# Blueboard_Pro_v1_0.net
KiCad netlist of a schematic drawn in EAGLE
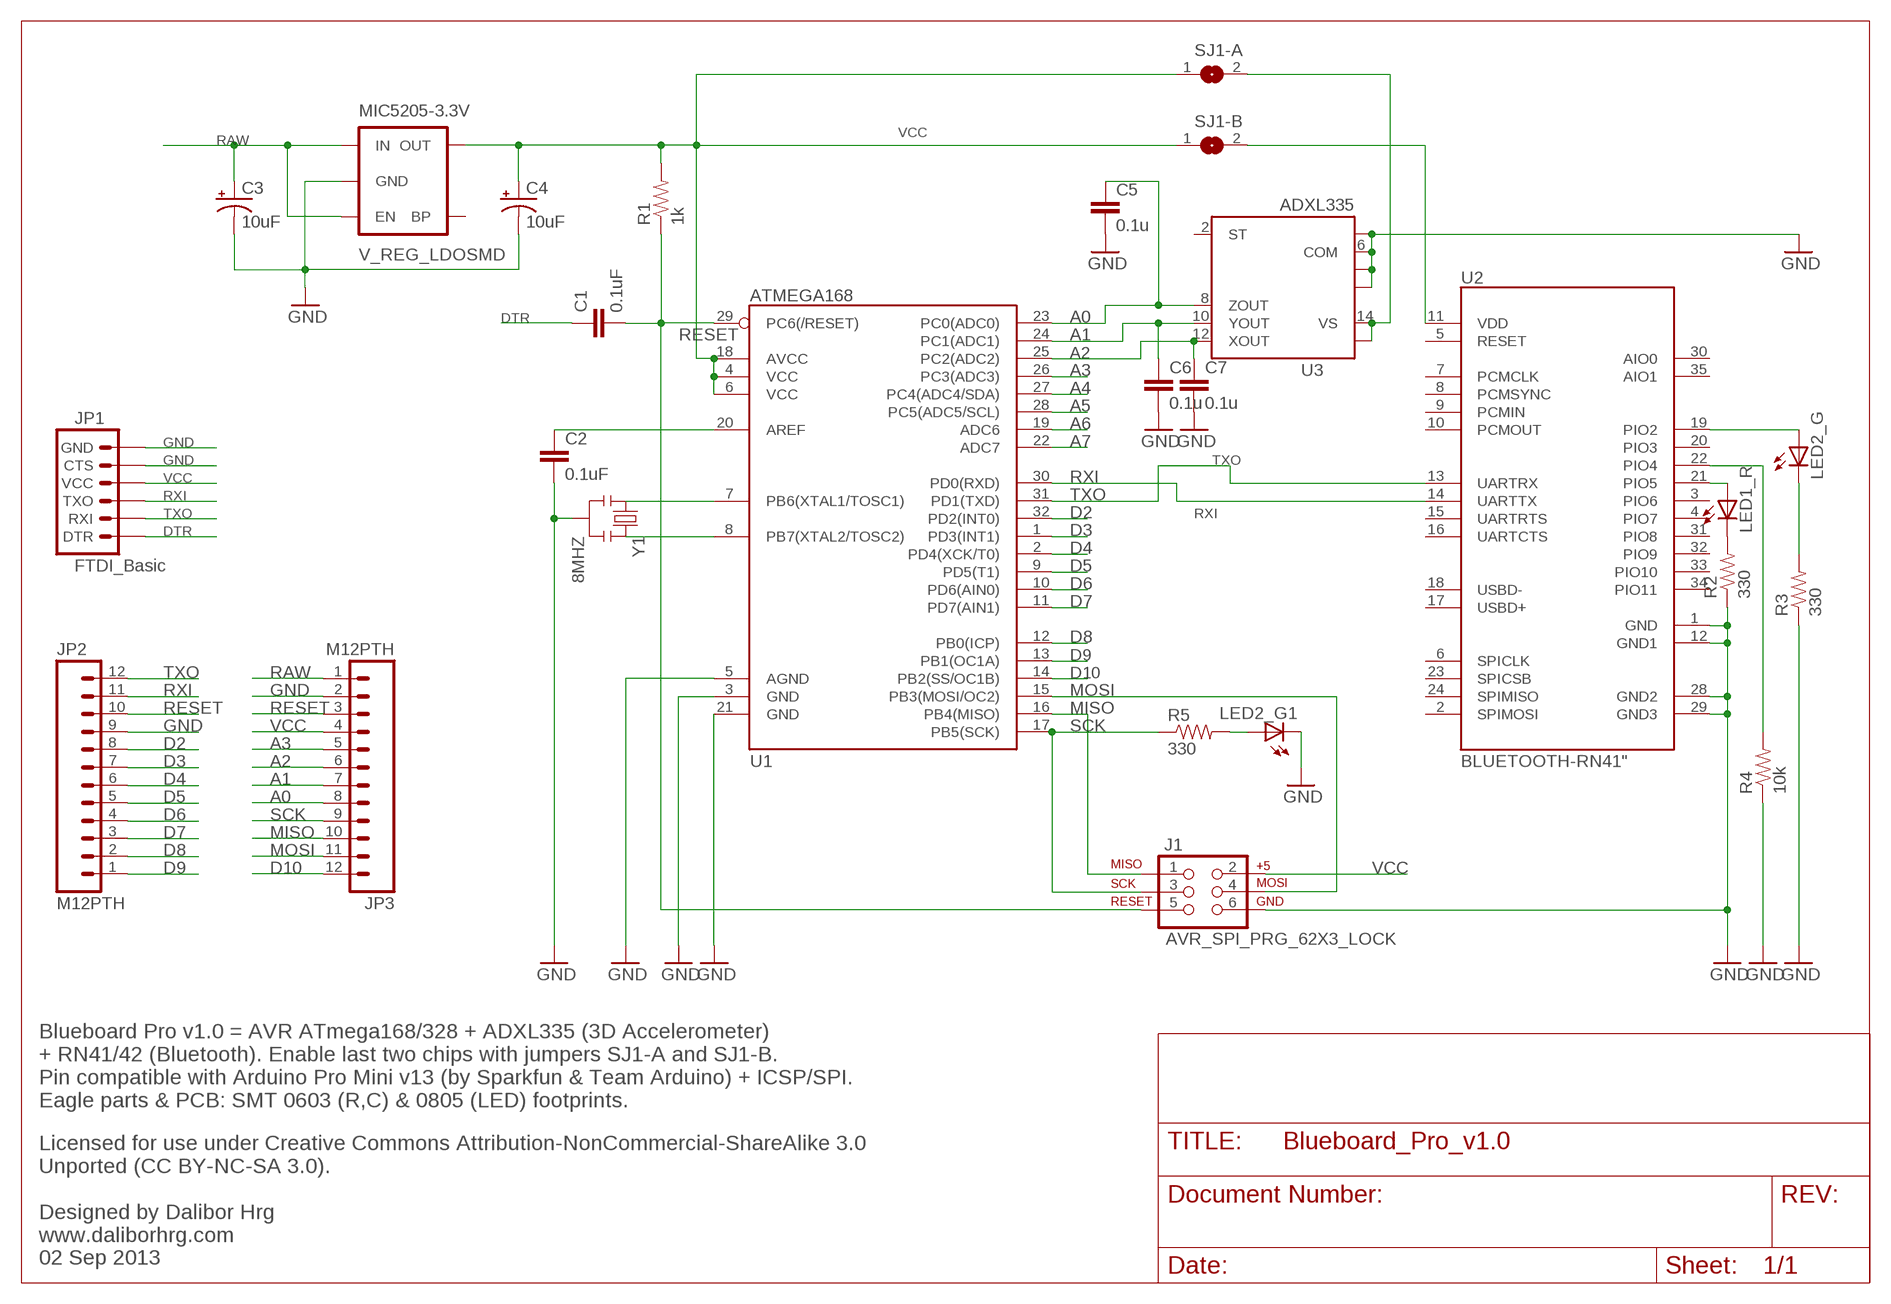
[diagram p0: schematic, sheet 1]

(export (version "E")
  (design (tool "Eeschema 10.0.6"))
  (components
    (comp (ref "C1")
      (value "0.1uF")
      (footprint "eagle-import:0603-CAP")
      (libsource (lib "eagle-import") (part "SparkFun-Passives_CAP0603-CAP"))
    )
    (comp (ref "C2")
      (value "0.1uF")
      (footprint "eagle-import:0603-CAP")
      (libsource (lib "eagle-import") (part "CAP0603-CAP"))
    )
    (comp (ref "C3")
      (value "10uF")
      (footprint "eagle-import:EIA3216")
      (libsource (lib "eagle-import") (part "10UF-16V-10%(TANT)"))
    )
    (comp (ref "C4")
      (value "10uF")
      (footprint "eagle-import:EIA3216")
      (libsource (lib "eagle-import") (part "10UF-16V-10%(TANT)"))
    )
    (comp (ref "C5")
      (value "0.1u")
      (footprint "eagle-import:0603-CAP")
      (libsource (lib "eagle-import") (part "SparkFun-Passives_CAP0603-CAP"))
    )
    (comp (ref "C6")
      (value "0.1u")
      (footprint "eagle-import:0603-CAP")
      (libsource (lib "eagle-import") (part "SparkFun-Passives_CAP0603-CAP"))
    )
    (comp (ref "C7")
      (value "0.1u")
      (footprint "eagle-import:0603-CAP")
      (libsource (lib "eagle-import") (part "SparkFun-Passives_CAP0603-CAP"))
    )
    (comp (ref "J1")
      (value "AVR_SPI_PRG_62X3_LOCK")
      (footprint "eagle-import:2X3_LOCK")
      (libsource (lib "eagle-import") (part "AVR_SPI_PRG_62X3_LOCK"))
    )
    (comp (ref "JP1")
      (value "FTDI_Basic")
      (footprint "eagle-import:1X06")
      (libsource (lib "eagle-import") (part "ARDUINO_SERIAL_PROGRAMPTH"))
    )
    (comp (ref "JP2")
      (value "M12PTH")
      (footprint "eagle-import:1X12")
      (libsource (lib "eagle-import") (part "M12PTH"))
    )
    (comp (ref "JP3")
      (value "M12PTH")
      (footprint "eagle-import:1X12")
      (libsource (lib "eagle-import") (part "M12PTH"))
    )
    (comp (ref "LED1_R")
      (value "LEDCHIP-LED0805")
      (footprint "eagle-import:CHIP-LED0805")
      (libsource (lib "eagle-import") (part "LEDCHIP-LED0805"))
    )
    (comp (ref "LED2_G")
      (value "LEDCHIP-LED0805")
      (footprint "eagle-import:CHIP-LED0805")
      (libsource (lib "eagle-import") (part "LEDCHIP-LED0805"))
    )
    (comp (ref "LED2_G1")
      (value "LEDCHIP-LED0805")
      (footprint "eagle-import:CHIP-LED0805")
      (libsource (lib "eagle-import") (part "LEDCHIP-LED0805"))
    )
    (comp (ref "MIC5205-3.3V")
      (value "V_REG_LDOSMD")
      (footprint "eagle-import:SOT23-5")
      (libsource (lib "eagle-import") (part "V_REG_LDOSMD"))
    )
    (comp (ref "R1")
      (value "1k")
      (footprint "eagle-import:0603-RES")
      (libsource (lib "eagle-import") (part "1K-1%"))
    )
    (comp (ref "R2")
      (value "330")
      (footprint "eagle-import:0603-RES")
      (libsource (lib "eagle-import") (part "RESISTOR0603-RES"))
    )
    (comp (ref "R3")
      (value "330")
      (footprint "eagle-import:0603-RES")
      (libsource (lib "eagle-import") (part "RESISTOR0603-RES"))
    )
    (comp (ref "R4")
      (value "10k")
      (footprint "eagle-import:0603-RES")
      (libsource (lib "eagle-import") (part "RESISTOR0603"))
    )
    (comp (ref "R5")
      (value "330")
      (footprint "eagle-import:0603-RES")
      (libsource (lib "eagle-import") (part "RESISTOR0603-RES"))
    )
    (comp (ref "SJ1-A")
      (value "SJ")
      (footprint "eagle-import:SJ")
      (libsource (lib "eagle-import") (part "SJ"))
    )
    (comp (ref "SJ1-B")
      (value "SJ")
      (footprint "eagle-import:SJ")
      (libsource (lib "eagle-import") (part "SJ"))
    )
    (comp (ref "U1")
      (value "ATMEGA168")
      (footprint "eagle-import:TQFP32-08")
      (libsource (lib "eagle-import") (part "ATMEGA168"))
    )
    (comp (ref "U2")
      (value "BLUETOOTH-RN41\"")
      (footprint "eagle-import:RN41")
      (libsource (lib "eagle-import") (part "BLUETOOTH-RN41{dblquote}"))
    )
    (comp (ref "U3")
      (value "ADXL335")
      (footprint "eagle-import:LFCSP-16")
      (libsource (lib "eagle-import") (part "ADXL335"))
    )
    (comp (ref "Y1")
      (value "8MHZ")
      (footprint "eagle-import:RESONATOR-SMD")
      (libsource (lib "eagle-import") (part "RESONATOR8MHZ"))
    )
  )
  (nets
    (net (code "1") (name "/A0") (class "Default")
      (node (ref "C5") (pin "1") (pinfunction "1_1") (pintype "passive"))
      (node (ref "JP3") (pin "8") (pinfunction "8_8") (pintype "passive"))
      (node (ref "U1") (pin "23") (pinfunction "PC0(ADC0)_23") (pintype "bidirectional"))
      (node (ref "U3") (pin "8") (pinfunction "ZOUT_8") (pintype "bidirectional"))
    )
    (net (code "2") (name "/A1") (class "Default")
      (node (ref "C6") (pin "1") (pinfunction "1_1") (pintype "passive"))
      (node (ref "JP3") (pin "7") (pinfunction "7_7") (pintype "passive"))
      (node (ref "U1") (pin "24") (pinfunction "PC1(ADC1)_24") (pintype "bidirectional"))
      (node (ref "U3") (pin "10") (pinfunction "YOUT_10") (pintype "bidirectional"))
    )
    (net (code "3") (name "/A2") (class "Default")
      (node (ref "C7") (pin "1") (pinfunction "1_1") (pintype "passive"))
      (node (ref "JP3") (pin "6") (pinfunction "6_6") (pintype "passive"))
      (node (ref "U1") (pin "25") (pinfunction "PC2(ADC2)_25") (pintype "bidirectional"))
      (node (ref "U3") (pin "12") (pinfunction "XOUT_12") (pintype "bidirectional"))
    )
    (net (code "4") (name "/A3") (class "Default")
      (node (ref "JP3") (pin "5") (pinfunction "5_5") (pintype "passive"))
      (node (ref "U1") (pin "26") (pinfunction "PC3(ADC3)_26") (pintype "bidirectional"))
    )
    (net (code "5") (name "/A4") (class "Default")
      (node (ref "U1") (pin "27") (pinfunction "PC4(ADC4/SDA)_27") (pintype "bidirectional"))
    )
    (net (code "6") (name "/A5") (class "Default")
      (node (ref "U1") (pin "28") (pinfunction "PC5(ADC5/SCL)_28") (pintype "bidirectional"))
    )
    (net (code "7") (name "/A6") (class "Default")
      (node (ref "U1") (pin "19") (pinfunction "ADC6_19") (pintype "bidirectional"))
    )
    (net (code "8") (name "/A7") (class "Default")
      (node (ref "U1") (pin "22") (pinfunction "ADC7_22") (pintype "bidirectional"))
    )
    (net (code "9") (name "/D2") (class "Default")
      (node (ref "JP2") (pin "8") (pinfunction "8_8") (pintype "passive"))
      (node (ref "U1") (pin "32") (pinfunction "PD2(INT0)_32") (pintype "bidirectional"))
    )
    (net (code "10") (name "/D3") (class "Default")
      (node (ref "JP2") (pin "7") (pinfunction "7_7") (pintype "passive"))
      (node (ref "U1") (pin "1") (pinfunction "PD3(INT1)_1") (pintype "bidirectional"))
    )
    (net (code "11") (name "/D4") (class "Default")
      (node (ref "JP2") (pin "6") (pinfunction "6_6") (pintype "passive"))
      (node (ref "U1") (pin "2") (pinfunction "PD4(XCK/T0)_2") (pintype "bidirectional"))
    )
    (net (code "12") (name "/D5") (class "Default")
      (node (ref "JP2") (pin "5") (pinfunction "5_5") (pintype "passive"))
      (node (ref "U1") (pin "9") (pinfunction "PD5(T1)_9") (pintype "bidirectional"))
    )
    (net (code "13") (name "/D6") (class "Default")
      (node (ref "JP2") (pin "4") (pinfunction "4_4") (pintype "passive"))
      (node (ref "U1") (pin "10") (pinfunction "PD6(AIN0)_10") (pintype "bidirectional"))
    )
    (net (code "14") (name "/D7") (class "Default")
      (node (ref "JP2") (pin "3") (pinfunction "3_3") (pintype "passive"))
      (node (ref "U1") (pin "11") (pinfunction "PD7(AIN1)_11") (pintype "bidirectional"))
    )
    (net (code "15") (name "/D8") (class "Default")
      (node (ref "JP2") (pin "2") (pinfunction "2_2") (pintype "passive"))
      (node (ref "U1") (pin "12") (pinfunction "PB0(ICP)_12") (pintype "bidirectional"))
    )
    (net (code "16") (name "/D9") (class "Default")
      (node (ref "JP2") (pin "1") (pinfunction "1_1") (pintype "passive"))
      (node (ref "U1") (pin "13") (pinfunction "PB1(OC1A)_13") (pintype "bidirectional"))
    )
    (net (code "17") (name "/D10") (class "Default")
      (node (ref "JP3") (pin "12") (pinfunction "12_12") (pintype "passive"))
      (node (ref "U1") (pin "14") (pinfunction "PB2(SS/OC1B)_14") (pintype "bidirectional"))
    )
    (net (code "18") (name "/DTR") (class "Default")
      (node (ref "C1") (pin "1") (pinfunction "1_1") (pintype "passive"))
      (node (ref "JP1") (pin "1") (pinfunction "DTR_1") (pintype "passive"))
    )
    (net (code "19") (name "/MISO") (class "Default")
      (node (ref "J1") (pin "1") (pinfunction "1_1") (pintype "passive"))
      (node (ref "JP3") (pin "10") (pinfunction "10_10") (pintype "passive"))
      (node (ref "U1") (pin "16") (pinfunction "PB4(MISO)_16") (pintype "bidirectional"))
    )
    (net (code "20") (name "/MOSI") (class "Default")
      (node (ref "J1") (pin "4") (pinfunction "4_4") (pintype "passive"))
      (node (ref "JP3") (pin "11") (pinfunction "11_11") (pintype "passive"))
      (node (ref "U1") (pin "15") (pinfunction "PB3(MOSI/OC2)_15") (pintype "bidirectional"))
    )
    (net (code "21") (name "/RAW") (class "Default")
      (node (ref "C3") (pin "A") (pinfunction "+_A") (pintype "passive"))
      (node (ref "JP3") (pin "1") (pinfunction "1_1") (pintype "passive"))
      (node (ref "MIC5205-3.3V") (pin "1") (pinfunction "IN_1") (pintype "input"))
      (node (ref "MIC5205-3.3V") (pin "3") (pinfunction "EN_3") (pintype "input"))
    )
    (net (code "22") (name "/RESET") (class "Default")
      (node (ref "C1") (pin "2") (pinfunction "2_2") (pintype "passive"))
      (node (ref "J1") (pin "5") (pinfunction "5_5") (pintype "passive"))
      (node (ref "JP2") (pin "10") (pinfunction "10_10") (pintype "passive"))
      (node (ref "JP3") (pin "3") (pinfunction "3_3") (pintype "passive"))
      (node (ref "R1") (pin "1") (pinfunction "1_1") (pintype "passive"))
      (node (ref "U1") (pin "29") (pinfunction "PC6(/RESET)_29") (pintype "bidirectional"))
    )
    (net (code "23") (name "/RXI") (class "Default")
      (node (ref "JP1") (pin "3") (pinfunction "TXO_3") (pintype "passive"))
      (node (ref "JP2") (pin "11") (pinfunction "11_11") (pintype "passive"))
      (node (ref "U1") (pin "30") (pinfunction "PD0(RXD)_30") (pintype "bidirectional"))
      (node (ref "U2") (pin "14") (pinfunction "UARTTX_14") (pintype "bidirectional"))
    )
    (net (code "24") (name "/SCK") (class "Default")
      (node (ref "J1") (pin "3") (pinfunction "3_3") (pintype "passive"))
      (node (ref "JP3") (pin "9") (pinfunction "9_9") (pintype "passive"))
      (node (ref "R5") (pin "1") (pinfunction "1_1") (pintype "passive"))
      (node (ref "U1") (pin "17") (pinfunction "PB5(SCK)_17") (pintype "bidirectional"))
    )
    (net (code "25") (name "/TXO") (class "Default")
      (node (ref "JP1") (pin "2") (pinfunction "RXI_2") (pintype "passive"))
      (node (ref "JP2") (pin "12") (pinfunction "12_12") (pintype "passive"))
      (node (ref "U1") (pin "31") (pinfunction "PD1(TXD)_31") (pintype "bidirectional"))
      (node (ref "U2") (pin "13") (pinfunction "UARTRX_13") (pintype "bidirectional"))
    )
    (net (code "26") (name "/VCC") (class "Default")
      (node (ref "C4") (pin "A") (pinfunction "+_A") (pintype "passive"))
      (node (ref "J1") (pin "2") (pinfunction "2_2") (pintype "passive"))
      (node (ref "JP1") (pin "4") (pinfunction "VCC_4") (pintype "passive"))
      (node (ref "JP3") (pin "4") (pinfunction "4_4") (pintype "passive"))
      (node (ref "MIC5205-3.3V") (pin "5") (pinfunction "OUT_5") (pintype "passive"))
      (node (ref "R1") (pin "2") (pinfunction "2_2") (pintype "passive"))
      (node (ref "SJ1-A") (pin "1") (pinfunction "1_1") (pintype "passive"))
      (node (ref "SJ1-B") (pin "1") (pinfunction "1_1") (pintype "passive"))
      (node (ref "U1") (pin "18") (pinfunction "AVCC_18") (pintype "bidirectional"))
      (node (ref "U1") (pin "4") (pinfunction "VCC_4") (pintype "bidirectional"))
      (node (ref "U1") (pin "6") (pinfunction "VCC_6") (pintype "bidirectional"))
    )
    (net (code "27") (name "GND") (class "Default")
      (node (ref "C2") (pin "2") (pinfunction "2_2") (pintype "passive"))
      (node (ref "C3") (pin "C") (pinfunction "-_C") (pintype "passive"))
      (node (ref "C4") (pin "C") (pinfunction "-_C") (pintype "passive"))
      (node (ref "C5") (pin "2") (pinfunction "2_2") (pintype "passive"))
      (node (ref "C6") (pin "2") (pinfunction "2_2") (pintype "passive"))
      (node (ref "C7") (pin "2") (pinfunction "2_2") (pintype "passive"))
      (node (ref "J1") (pin "6") (pinfunction "6_6") (pintype "passive"))
      (node (ref "JP1") (pin "5") (pinfunction "CTS_5") (pintype "passive"))
      (node (ref "JP1") (pin "6") (pinfunction "GND_6") (pintype "passive"))
      (node (ref "JP2") (pin "9") (pinfunction "9_9") (pintype "passive"))
      (node (ref "JP3") (pin "2") (pinfunction "2_2") (pintype "passive"))
      (node (ref "LED2_G1") (pin "C") (pinfunction "C_C") (pintype "passive"))
      (node (ref "MIC5205-3.3V") (pin "2") (pinfunction "GND_2") (pintype "input"))
      (node (ref "R2") (pin "1") (pinfunction "1_1") (pintype "passive"))
      (node (ref "R3") (pin "1") (pinfunction "1_1") (pintype "passive"))
      (node (ref "R4") (pin "1") (pinfunction "1_1") (pintype "passive"))
      (node (ref "U1") (pin "21") (pinfunction "GND_21") (pintype "bidirectional"))
      (node (ref "U1") (pin "3") (pinfunction "GND_3") (pintype "bidirectional"))
      (node (ref "U1") (pin "5") (pinfunction "AGND_5") (pintype "bidirectional"))
      (node (ref "U2") (pin "1") (pinfunction "GND_1") (pintype "bidirectional"))
      (node (ref "U2") (pin "12") (pinfunction "GND1_12") (pintype "bidirectional"))
      (node (ref "U2") (pin "28") (pinfunction "GND2_28") (pintype "bidirectional"))
      (node (ref "U2") (pin "29") (pinfunction "GND3_29") (pintype "bidirectional"))
      (node (ref "U3") (pin "3") (pinfunction "COM_3") (pintype "bidirectional"))
      (node (ref "U3") (pin "5") (pinfunction "COM_5") (pintype "bidirectional"))
      (node (ref "U3") (pin "6") (pinfunction "COM_6") (pintype "bidirectional"))
      (node (ref "U3") (pin "7") (pinfunction "COM_7") (pintype "bidirectional"))
      (node (ref "Y1") (pin "2") (pinfunction "2_2") (pintype "passive"))
    )
    (net (code "28") (name "Net-(LED1_R-PadC)") (class "Default")
      (node (ref "LED1_R") (pin "C") (pinfunction "C_C") (pintype "passive"))
      (node (ref "R2") (pin "2") (pinfunction "2_2") (pintype "passive"))
    )
    (net (code "29") (name "Net-(LED2_G-PadC)") (class "Default")
      (node (ref "LED2_G") (pin "C") (pinfunction "C_C") (pintype "passive"))
      (node (ref "R3") (pin "2") (pinfunction "2_2") (pintype "passive"))
    )
    (net (code "30") (name "Net-(LED2_G1-PadA)") (class "Default")
      (node (ref "LED2_G1") (pin "A") (pinfunction "A_A") (pintype "passive"))
      (node (ref "R5") (pin "2") (pinfunction "2_2") (pintype "passive"))
    )
    (net (code "31") (name "Net-(SJ1-A-Pad2)") (class "Default")
      (node (ref "SJ1-A") (pin "2") (pinfunction "2_2") (pintype "passive"))
      (node (ref "U3") (pin "14") (pinfunction "VS_14") (pintype "bidirectional"))
      (node (ref "U3") (pin "15") (pinfunction "VS_15") (pintype "bidirectional"))
    )
    (net (code "32") (name "Net-(U1-AREF)") (class "Default")
      (node (ref "C2") (pin "1") (pinfunction "1_1") (pintype "passive"))
      (node (ref "U1") (pin "20") (pinfunction "AREF_20") (pintype "bidirectional"))
    )
    (net (code "33") (name "Net-(U1-PB6(XTAL1{slash}TOSC1))") (class "Default")
      (node (ref "U1") (pin "7") (pinfunction "PB6(XTAL1/TOSC1)_7") (pintype "bidirectional"))
      (node (ref "Y1") (pin "1") (pinfunction "1_1") (pintype "passive"))
    )
    (net (code "34") (name "Net-(U1-PB7(XTAL2{slash}TOSC2))") (class "Default")
      (node (ref "U1") (pin "8") (pinfunction "PB7(XTAL2/TOSC2)_8") (pintype "bidirectional"))
      (node (ref "Y1") (pin "3") (pinfunction "3_3") (pintype "passive"))
    )
    (net (code "35") (name "Net-(U2-PIO2)") (class "Default")
      (node (ref "LED2_G") (pin "A") (pinfunction "A_A") (pintype "passive"))
      (node (ref "U2") (pin "19") (pinfunction "PIO2_19") (pintype "bidirectional"))
    )
    (net (code "36") (name "Net-(U2-PIO4)") (class "Default")
      (node (ref "R4") (pin "2") (pinfunction "2_2") (pintype "passive"))
      (node (ref "U2") (pin "22") (pinfunction "PIO4_22") (pintype "bidirectional"))
    )
    (net (code "37") (name "Net-(U2-PIO5)") (class "Default")
      (node (ref "LED1_R") (pin "A") (pinfunction "A_A") (pintype "passive"))
      (node (ref "U2") (pin "21") (pinfunction "PIO5_21") (pintype "bidirectional"))
    )
    (net (code "38") (name "Net-(U2-VDD)") (class "Default")
      (node (ref "SJ1-B") (pin "2") (pinfunction "2_2") (pintype "passive"))
      (node (ref "U2") (pin "11") (pinfunction "VDD_11") (pintype "bidirectional"))
    )
    (net (code "39") (name "unconnected-(MIC5205-3.3V-BP-Pad4)") (class "Default")
      (node (ref "MIC5205-3.3V") (pin "4") (pinfunction "BP_4") (pintype "input"))
    )
    (net (code "40") (name "unconnected-(U2-AIO0-Pad30)") (class "Default")
      (node (ref "U2") (pin "30") (pinfunction "AIO0_30") (pintype "bidirectional"))
    )
    (net (code "41") (name "unconnected-(U2-AIO1-Pad35)") (class "Default")
      (node (ref "U2") (pin "35") (pinfunction "AIO1_35") (pintype "bidirectional"))
    )
    (net (code "42") (name "unconnected-(U2-PCMCLK-Pad7)") (class "Default")
      (node (ref "U2") (pin "7") (pinfunction "PCMCLK_7") (pintype "bidirectional"))
    )
    (net (code "43") (name "unconnected-(U2-PCMIN-Pad9)") (class "Default")
      (node (ref "U2") (pin "9") (pinfunction "PCMIN_9") (pintype "bidirectional"))
    )
    (net (code "44") (name "unconnected-(U2-PCMOUT-Pad10)") (class "Default")
      (node (ref "U2") (pin "10") (pinfunction "PCMOUT_10") (pintype "bidirectional"))
    )
    (net (code "45") (name "unconnected-(U2-PCMSYNC-Pad8)") (class "Default")
      (node (ref "U2") (pin "8") (pinfunction "PCMSYNC_8") (pintype "bidirectional"))
    )
    (net (code "46") (name "unconnected-(U2-PIO3-Pad20)") (class "Default")
      (node (ref "U2") (pin "20") (pinfunction "PIO3_20") (pintype "bidirectional"))
    )
    (net (code "47") (name "unconnected-(U2-PIO6-Pad3)") (class "Default")
      (node (ref "U2") (pin "3") (pinfunction "PIO6_3") (pintype "bidirectional"))
    )
    (net (code "48") (name "unconnected-(U2-PIO7-Pad4)") (class "Default")
      (node (ref "U2") (pin "4") (pinfunction "PIO7_4") (pintype "bidirectional"))
    )
    (net (code "49") (name "unconnected-(U2-PIO8-Pad31)") (class "Default")
      (node (ref "U2") (pin "31") (pinfunction "PIO8_31") (pintype "bidirectional"))
    )
    (net (code "50") (name "unconnected-(U2-PIO9-Pad32)") (class "Default")
      (node (ref "U2") (pin "32") (pinfunction "PIO9_32") (pintype "bidirectional"))
    )
    (net (code "51") (name "unconnected-(U2-PIO10-Pad33)") (class "Default")
      (node (ref "U2") (pin "33") (pinfunction "PIO10_33") (pintype "bidirectional"))
    )
    (net (code "52") (name "unconnected-(U2-PIO11-Pad34)") (class "Default")
      (node (ref "U2") (pin "34") (pinfunction "PIO11_34") (pintype "bidirectional"))
    )
    (net (code "53") (name "unconnected-(U2-RESET-Pad5)") (class "Default")
      (node (ref "U2") (pin "5") (pinfunction "RESET_5") (pintype "bidirectional"))
    )
    (net (code "54") (name "unconnected-(U2-SPICLK-Pad6)") (class "Default")
      (node (ref "U2") (pin "6") (pinfunction "SPICLK_6") (pintype "bidirectional"))
    )
    (net (code "55") (name "unconnected-(U2-SPICSB-Pad23)") (class "Default")
      (node (ref "U2") (pin "23") (pinfunction "SPICSB_23") (pintype "bidirectional"))
    )
    (net (code "56") (name "unconnected-(U2-SPIMISO-Pad24)") (class "Default")
      (node (ref "U2") (pin "24") (pinfunction "SPIMISO_24") (pintype "bidirectional"))
    )
    (net (code "57") (name "unconnected-(U2-SPIMOSI-Pad2)") (class "Default")
      (node (ref "U2") (pin "2") (pinfunction "SPIMOSI_2") (pintype "bidirectional"))
    )
    (net (code "58") (name "unconnected-(U2-UARTCTS-Pad16)") (class "Default")
      (node (ref "U2") (pin "16") (pinfunction "UARTCTS_16") (pintype "bidirectional"))
    )
    (net (code "59") (name "unconnected-(U2-UARTRTS-Pad15)") (class "Default")
      (node (ref "U2") (pin "15") (pinfunction "UARTRTS_15") (pintype "bidirectional"))
    )
    (net (code "60") (name "unconnected-(U2-USBD+-Pad17)") (class "Default")
      (node (ref "U2") (pin "17") (pinfunction "USBD+_17") (pintype "bidirectional"))
    )
    (net (code "61") (name "unconnected-(U2-USBD--Pad18)") (class "Default")
      (node (ref "U2") (pin "18") (pinfunction "USBD-_18") (pintype "bidirectional"))
    )
    (net (code "62") (name "unconnected-(U3-ST-Pad2)") (class "Default")
      (node (ref "U3") (pin "2") (pinfunction "ST_2") (pintype "bidirectional"))
    )
  )
)
